# BumpSensors.net
KiCad netlist of a schematic drawn in Altium Designer
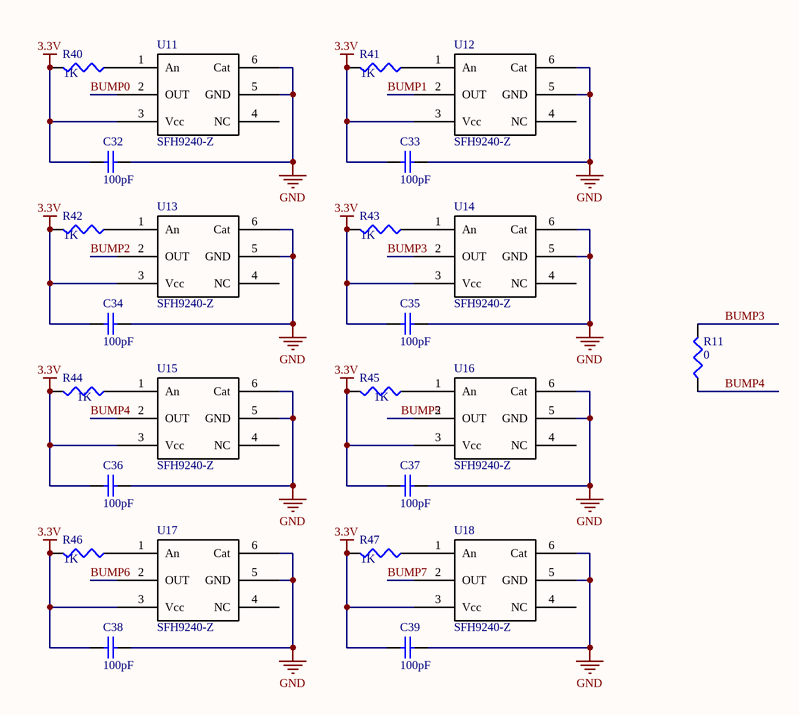
[diagram p0: BumpSensors.SchDoc]

(export (version "E")
  (design (tool "Eeschema 10.0.6"))
  (components
    (comp (ref "C32")
      (value "100pF")
      (footprint "CAPC1005L")
      (description "Capacitor (Semiconductor SIM Model)")
      (fields (field (name "Comment") "Cap Semi") (field (name "PUBLISHER") "Altium Limited"))
      (libsource (lib "Miscellaneous Devices") (part "Cap Semi"))
    )
    (comp (ref "C33")
      (value "100pF")
      (footprint "CAPC1005L")
      (description "Capacitor (Semiconductor SIM Model)")
      (fields (field (name "Comment") "Cap Semi") (field (name "PUBLISHER") "Altium Limited"))
      (libsource (lib "Miscellaneous Devices") (part "Cap Semi"))
    )
    (comp (ref "C34")
      (value "100pF")
      (footprint "CAPC1005L")
      (description "Capacitor (Semiconductor SIM Model)")
      (fields (field (name "Comment") "Cap Semi") (field (name "PUBLISHER") "Altium Limited"))
      (libsource (lib "Miscellaneous Devices") (part "Cap Semi"))
    )
    (comp (ref "C35")
      (value "100pF")
      (footprint "CAPC1005L")
      (description "Capacitor (Semiconductor SIM Model)")
      (fields (field (name "Comment") "Cap Semi") (field (name "PUBLISHER") "Altium Limited"))
      (libsource (lib "Miscellaneous Devices") (part "Cap Semi"))
    )
    (comp (ref "C36")
      (value "100pF")
      (footprint "CAPC1005L")
      (description "Capacitor (Semiconductor SIM Model)")
      (fields (field (name "Comment") "Cap Semi") (field (name "PUBLISHER") "Altium Limited"))
      (libsource (lib "Miscellaneous Devices") (part "Cap Semi"))
    )
    (comp (ref "C37")
      (value "100pF")
      (footprint "CAPC1005L")
      (description "Capacitor (Semiconductor SIM Model)")
      (fields (field (name "Comment") "Cap Semi") (field (name "PUBLISHER") "Altium Limited"))
      (libsource (lib "Miscellaneous Devices") (part "Cap Semi"))
    )
    (comp (ref "C38")
      (value "100pF")
      (footprint "CAPC1005L")
      (description "Capacitor (Semiconductor SIM Model)")
      (fields (field (name "Comment") "Cap Semi") (field (name "PUBLISHER") "Altium Limited"))
      (libsource (lib "Miscellaneous Devices") (part "Cap Semi"))
    )
    (comp (ref "C39")
      (value "100pF")
      (footprint "CAPC1005L")
      (description "Capacitor (Semiconductor SIM Model)")
      (fields (field (name "Comment") "Cap Semi") (field (name "PUBLISHER") "Altium Limited"))
      (libsource (lib "Miscellaneous Devices") (part "Cap Semi"))
    )
    (comp (ref "R11")
      (value "0")
      (footprint "RESC1608L")
      (description "Resistor")
      (fields (field (name "Comment") "Res3") (field (name "PUBLISHER") "Altium Limited"))
      (libsource (lib "Miscellaneous Devices") (part "Res3"))
    )
    (comp (ref "R40")
      (value "1K")
      (footprint "RESC1608L")
      (description "Resistor")
      (fields (field (name "Comment") "Res3") (field (name "PUBLISHER") "Altium Limited"))
      (libsource (lib "Miscellaneous Devices") (part "Res3"))
    )
    (comp (ref "R41")
      (value "1K")
      (footprint "RESC1608L")
      (description "Resistor")
      (fields (field (name "Comment") "Res3") (field (name "PUBLISHER") "Altium Limited"))
      (libsource (lib "Miscellaneous Devices") (part "Res3"))
    )
    (comp (ref "R42")
      (value "1K")
      (footprint "RESC1608L")
      (description "Resistor")
      (fields (field (name "Comment") "Res3") (field (name "PUBLISHER") "Altium Limited"))
      (libsource (lib "Miscellaneous Devices") (part "Res3"))
    )
    (comp (ref "R43")
      (value "1K")
      (footprint "RESC1608L")
      (description "Resistor")
      (fields (field (name "Comment") "Res3") (field (name "PUBLISHER") "Altium Limited"))
      (libsource (lib "Miscellaneous Devices") (part "Res3"))
    )
    (comp (ref "R44")
      (value "1K")
      (footprint "RESC1608L")
      (description "Resistor")
      (fields (field (name "Comment") "Res3") (field (name "PUBLISHER") "Altium Limited"))
      (libsource (lib "Miscellaneous Devices") (part "Res3"))
    )
    (comp (ref "R45")
      (value "1K")
      (footprint "RESC1608L")
      (description "Resistor")
      (fields (field (name "Comment") "Res3") (field (name "PUBLISHER") "Altium Limited"))
      (libsource (lib "Miscellaneous Devices") (part "Res3"))
    )
    (comp (ref "R46")
      (value "1K")
      (footprint "RESC1608L")
      (description "Resistor")
      (fields (field (name "Comment") "Res3") (field (name "PUBLISHER") "Altium Limited"))
      (libsource (lib "Miscellaneous Devices") (part "Res3"))
    )
    (comp (ref "R47")
      (value "1K")
      (footprint "RESC1608L")
      (description "Resistor")
      (fields (field (name "Comment") "Res3") (field (name "PUBLISHER") "Altium Limited"))
      (libsource (lib "Miscellaneous Devices") (part "Res3"))
    )
    (comp (ref "U11")
      (value "SFH9240-Z")
      (footprint "SFH9240-Z")
      (libsource (lib "mrone") (part "SFH9240-Z"))
    )
    (comp (ref "U12")
      (value "SFH9240-Z")
      (footprint "SFH9240-Z")
      (libsource (lib "mrone") (part "SFH9240-Z"))
    )
    (comp (ref "U13")
      (value "SFH9240-Z")
      (footprint "SFH9240-Z")
      (libsource (lib "mrone") (part "SFH9240-Z"))
    )
    (comp (ref "U14")
      (value "SFH9240-Z")
      (footprint "SFH9240-Z")
      (libsource (lib "mrone") (part "SFH9240-Z"))
    )
    (comp (ref "U15")
      (value "SFH9240-Z")
      (footprint "SFH9240-Z")
      (libsource (lib "mrone") (part "SFH9240-Z"))
    )
    (comp (ref "U16")
      (value "SFH9240-Z")
      (footprint "SFH9240-Z")
      (libsource (lib "mrone") (part "SFH9240-Z"))
    )
    (comp (ref "U17")
      (value "SFH9240-Z")
      (footprint "SFH9240-Z")
      (libsource (lib "mrone") (part "SFH9240-Z"))
    )
    (comp (ref "U18")
      (value "SFH9240-Z")
      (footprint "SFH9240-Z")
      (libsource (lib "mrone") (part "SFH9240-Z"))
    )
  )
  (nets
    (net (code "1") (name "/BUMP0") (class "Default")
      (node (ref "U11") (pin "2") (pinfunction "OUT_2") (pintype "passive"))
    )
    (net (code "2") (name "/BUMP1") (class "Default")
      (node (ref "U12") (pin "2") (pinfunction "OUT_2") (pintype "passive"))
    )
    (net (code "3") (name "/BUMP2") (class "Default")
      (node (ref "U13") (pin "2") (pinfunction "OUT_2") (pintype "passive"))
    )
    (net (code "4") (name "/BUMP3") (class "Default")
      (node (ref "R11") (pin "2") (pinfunction "2_2") (pintype "passive"))
      (node (ref "U14") (pin "2") (pinfunction "OUT_2") (pintype "passive"))
    )
    (net (code "5") (name "/BUMP4") (class "Default")
      (node (ref "R11") (pin "1") (pinfunction "1_1") (pintype "passive"))
      (node (ref "U15") (pin "2") (pinfunction "OUT_2") (pintype "passive"))
    )
    (net (code "6") (name "/BUMP5") (class "Default")
      (node (ref "U16") (pin "2") (pinfunction "OUT_2") (pintype "passive"))
    )
    (net (code "7") (name "/BUMP6") (class "Default")
      (node (ref "U17") (pin "2") (pinfunction "OUT_2") (pintype "passive"))
    )
    (net (code "8") (name "/BUMP7") (class "Default")
      (node (ref "U18") (pin "2") (pinfunction "OUT_2") (pintype "passive"))
    )
    (net (code "9") (name "3.3V") (class "Default")
      (node (ref "C32") (pin "2") (pinfunction "2_2") (pintype "passive"))
      (node (ref "C33") (pin "2") (pinfunction "2_2") (pintype "passive"))
      (node (ref "C34") (pin "2") (pinfunction "2_2") (pintype "passive"))
      (node (ref "C35") (pin "2") (pinfunction "2_2") (pintype "passive"))
      (node (ref "C36") (pin "2") (pinfunction "2_2") (pintype "passive"))
      (node (ref "C37") (pin "2") (pinfunction "2_2") (pintype "passive"))
      (node (ref "C38") (pin "2") (pinfunction "2_2") (pintype "passive"))
      (node (ref "C39") (pin "2") (pinfunction "2_2") (pintype "passive"))
      (node (ref "R40") (pin "2") (pinfunction "2_2") (pintype "passive"))
      (node (ref "R41") (pin "2") (pinfunction "2_2") (pintype "passive"))
      (node (ref "R42") (pin "2") (pinfunction "2_2") (pintype "passive"))
      (node (ref "R43") (pin "2") (pinfunction "2_2") (pintype "passive"))
      (node (ref "R44") (pin "2") (pinfunction "2_2") (pintype "passive"))
      (node (ref "R45") (pin "2") (pinfunction "2_2") (pintype "passive"))
      (node (ref "R46") (pin "2") (pinfunction "2_2") (pintype "passive"))
      (node (ref "R47") (pin "2") (pinfunction "2_2") (pintype "passive"))
      (node (ref "U11") (pin "3") (pinfunction "Vcc_3") (pintype "passive"))
      (node (ref "U12") (pin "3") (pinfunction "Vcc_3") (pintype "passive"))
      (node (ref "U13") (pin "3") (pinfunction "Vcc_3") (pintype "passive"))
      (node (ref "U14") (pin "3") (pinfunction "Vcc_3") (pintype "passive"))
      (node (ref "U15") (pin "3") (pinfunction "Vcc_3") (pintype "passive"))
      (node (ref "U16") (pin "3") (pinfunction "Vcc_3") (pintype "passive"))
      (node (ref "U17") (pin "3") (pinfunction "Vcc_3") (pintype "passive"))
      (node (ref "U18") (pin "3") (pinfunction "Vcc_3") (pintype "passive"))
    )
    (net (code "10") (name "GND") (class "Default")
      (node (ref "C32") (pin "1") (pinfunction "1_1") (pintype "passive"))
      (node (ref "C33") (pin "1") (pinfunction "1_1") (pintype "passive"))
      (node (ref "C34") (pin "1") (pinfunction "1_1") (pintype "passive"))
      (node (ref "C35") (pin "1") (pinfunction "1_1") (pintype "passive"))
      (node (ref "C36") (pin "1") (pinfunction "1_1") (pintype "passive"))
      (node (ref "C37") (pin "1") (pinfunction "1_1") (pintype "passive"))
      (node (ref "C38") (pin "1") (pinfunction "1_1") (pintype "passive"))
      (node (ref "C39") (pin "1") (pinfunction "1_1") (pintype "passive"))
      (node (ref "U11") (pin "5") (pinfunction "GND_5") (pintype "passive"))
      (node (ref "U11") (pin "6") (pinfunction "Cat_6") (pintype "passive"))
      (node (ref "U12") (pin "5") (pinfunction "GND_5") (pintype "passive"))
      (node (ref "U12") (pin "6") (pinfunction "Cat_6") (pintype "passive"))
      (node (ref "U13") (pin "5") (pinfunction "GND_5") (pintype "passive"))
      (node (ref "U13") (pin "6") (pinfunction "Cat_6") (pintype "passive"))
      (node (ref "U14") (pin "5") (pinfunction "GND_5") (pintype "passive"))
      (node (ref "U14") (pin "6") (pinfunction "Cat_6") (pintype "passive"))
      (node (ref "U15") (pin "5") (pinfunction "GND_5") (pintype "passive"))
      (node (ref "U15") (pin "6") (pinfunction "Cat_6") (pintype "passive"))
      (node (ref "U16") (pin "5") (pinfunction "GND_5") (pintype "passive"))
      (node (ref "U16") (pin "6") (pinfunction "Cat_6") (pintype "passive"))
      (node (ref "U17") (pin "5") (pinfunction "GND_5") (pintype "passive"))
      (node (ref "U17") (pin "6") (pinfunction "Cat_6") (pintype "passive"))
      (node (ref "U18") (pin "5") (pinfunction "GND_5") (pintype "passive"))
      (node (ref "U18") (pin "6") (pinfunction "Cat_6") (pintype "passive"))
    )
    (net (code "11") (name "Net-(U11-An)") (class "Default")
      (node (ref "R40") (pin "1") (pinfunction "1_1") (pintype "passive"))
      (node (ref "U11") (pin "1") (pinfunction "An_1") (pintype "passive"))
    )
    (net (code "12") (name "Net-(U12-An)") (class "Default")
      (node (ref "R41") (pin "1") (pinfunction "1_1") (pintype "passive"))
      (node (ref "U12") (pin "1") (pinfunction "An_1") (pintype "passive"))
    )
    (net (code "13") (name "Net-(U13-An)") (class "Default")
      (node (ref "R42") (pin "1") (pinfunction "1_1") (pintype "passive"))
      (node (ref "U13") (pin "1") (pinfunction "An_1") (pintype "passive"))
    )
    (net (code "14") (name "Net-(U14-An)") (class "Default")
      (node (ref "R43") (pin "1") (pinfunction "1_1") (pintype "passive"))
      (node (ref "U14") (pin "1") (pinfunction "An_1") (pintype "passive"))
    )
    (net (code "15") (name "Net-(U15-An)") (class "Default")
      (node (ref "R44") (pin "1") (pinfunction "1_1") (pintype "passive"))
      (node (ref "U15") (pin "1") (pinfunction "An_1") (pintype "passive"))
    )
    (net (code "16") (name "Net-(U16-An)") (class "Default")
      (node (ref "R45") (pin "1") (pinfunction "1_1") (pintype "passive"))
      (node (ref "U16") (pin "1") (pinfunction "An_1") (pintype "passive"))
    )
    (net (code "17") (name "Net-(U17-An)") (class "Default")
      (node (ref "R46") (pin "1") (pinfunction "1_1") (pintype "passive"))
      (node (ref "U17") (pin "1") (pinfunction "An_1") (pintype "passive"))
    )
    (net (code "18") (name "Net-(U18-An)") (class "Default")
      (node (ref "R47") (pin "1") (pinfunction "1_1") (pintype "passive"))
      (node (ref "U18") (pin "1") (pinfunction "An_1") (pintype "passive"))
    )
    (net (code "19") (name "unconnected-(U11-NC-Pad4)") (class "Default")
      (node (ref "U11") (pin "4") (pinfunction "NC_4") (pintype "passive"))
    )
    (net (code "20") (name "unconnected-(U12-NC-Pad4)") (class "Default")
      (node (ref "U12") (pin "4") (pinfunction "NC_4") (pintype "passive"))
    )
    (net (code "21") (name "unconnected-(U13-NC-Pad4)") (class "Default")
      (node (ref "U13") (pin "4") (pinfunction "NC_4") (pintype "passive"))
    )
    (net (code "22") (name "unconnected-(U14-NC-Pad4)") (class "Default")
      (node (ref "U14") (pin "4") (pinfunction "NC_4") (pintype "passive"))
    )
    (net (code "23") (name "unconnected-(U15-NC-Pad4)") (class "Default")
      (node (ref "U15") (pin "4") (pinfunction "NC_4") (pintype "passive"))
    )
    (net (code "24") (name "unconnected-(U16-NC-Pad4)") (class "Default")
      (node (ref "U16") (pin "4") (pinfunction "NC_4") (pintype "passive"))
    )
    (net (code "25") (name "unconnected-(U17-NC-Pad4)") (class "Default")
      (node (ref "U17") (pin "4") (pinfunction "NC_4") (pintype "passive"))
    )
    (net (code "26") (name "unconnected-(U18-NC-Pad4)") (class "Default")
      (node (ref "U18") (pin "4") (pinfunction "NC_4") (pintype "passive"))
    )
  )
)
